# power.net
KiCad netlist of a schematic drawn in Altium Designer
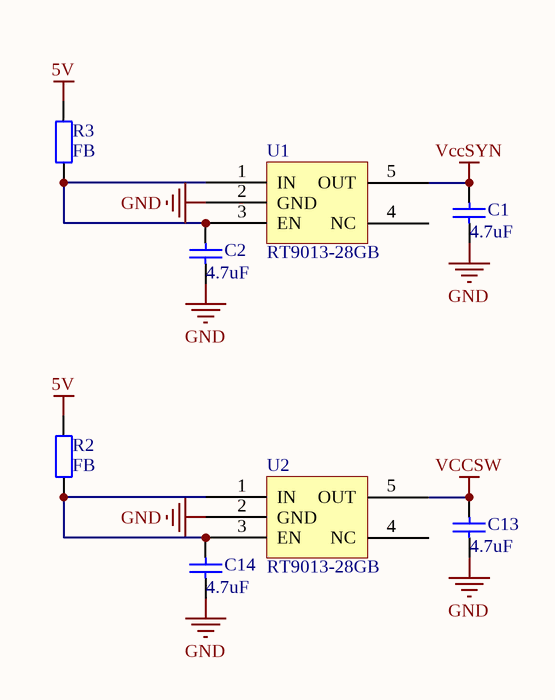
[diagram p0: power.SchDoc]

(export (version "E")
  (design (tool "Eeschema 10.0.6"))
  (components
    (comp (ref "C1")
      (value "4.7uF")
      (footprint "0603")
      (description "Capacitor")
      (fields (field (name "PUBLISHER") "Altium Limited"))
      (libsource (lib "RTC6705") (part "Cap"))
    )
    (comp (ref "C2")
      (value "4.7uF")
      (footprint "0603")
      (description "Capacitor")
      (fields (field (name "PUBLISHER") "Altium Limited"))
      (libsource (lib "RTC6705") (part "Cap"))
    )
    (comp (ref "C13")
      (value "4.7uF")
      (footprint "0603")
      (description "Capacitor")
      (fields (field (name "PUBLISHER") "Altium Limited"))
      (libsource (lib "RTC6705") (part "Cap"))
    )
    (comp (ref "C14")
      (value "4.7uF")
      (footprint "0603")
      (description "Capacitor")
      (fields (field (name "PUBLISHER") "Altium Limited"))
      (libsource (lib "RTC6705") (part "Cap"))
    )
    (comp (ref "R2")
      (value "FB")
      (footprint "0603")
      (description "Resistor")
      (fields (field (name "PUBLISHER") "Altium Limited"))
      (libsource (lib "Miscellaneous Devices") (part "Res2"))
    )
    (comp (ref "R3")
      (value "FB")
      (footprint "0603")
      (description "Resistor")
      (fields (field (name "PUBLISHER") "Altium Limited"))
      (libsource (lib "Miscellaneous Devices") (part "Res2"))
    )
    (comp (ref "U1") (value "RT9013-28GB") (footprint "SOT23-5") (libsource (lib "RTC6705") (part "LP5907")))
    (comp (ref "U2") (value "RT9013-28GB") (footprint "SOT23-5") (libsource (lib "RTC6705") (part "LP5907")))
  )
  (nets
    (net (code "1") (name "5V") (class "Default")
      (node (ref "R2") (pin "2") (pinfunction "2_2") (pintype "passive"))
      (node (ref "R3") (pin "2") (pinfunction "2_2") (pintype "passive"))
    )
    (net (code "2") (name "GND") (class "Default")
      (node (ref "C1") (pin "1") (pinfunction "1_1") (pintype "passive"))
      (node (ref "C13") (pin "1") (pinfunction "1_1") (pintype "passive"))
      (node (ref "C14") (pin "1") (pinfunction "1_1") (pintype "passive"))
      (node (ref "C2") (pin "1") (pinfunction "1_1") (pintype "passive"))
      (node (ref "U1") (pin "2") (pinfunction "GND_2") (pintype "passive"))
      (node (ref "U2") (pin "2") (pinfunction "GND_2") (pintype "passive"))
    )
    (net (code "3") (name "Net-(U1-EN)") (class "Default")
      (node (ref "C2") (pin "2") (pinfunction "2_2") (pintype "passive"))
      (node (ref "R3") (pin "1") (pinfunction "1_1") (pintype "passive"))
      (node (ref "U1") (pin "1") (pinfunction "IN_1") (pintype "passive"))
      (node (ref "U1") (pin "3") (pinfunction "EN_3") (pintype "passive"))
    )
    (net (code "4") (name "Net-(U2-EN)") (class "Default")
      (node (ref "C14") (pin "2") (pinfunction "2_2") (pintype "passive"))
      (node (ref "R2") (pin "1") (pinfunction "1_1") (pintype "passive"))
      (node (ref "U2") (pin "1") (pinfunction "IN_1") (pintype "passive"))
      (node (ref "U2") (pin "3") (pinfunction "EN_3") (pintype "passive"))
    )
    (net (code "5") (name "VCCSW") (class "Default")
      (node (ref "C13") (pin "2") (pinfunction "2_2") (pintype "passive"))
      (node (ref "U2") (pin "5") (pinfunction "OUT_5") (pintype "passive"))
    )
    (net (code "6") (name "VccSYN") (class "Default")
      (node (ref "C1") (pin "2") (pinfunction "2_2") (pintype "passive"))
      (node (ref "U1") (pin "5") (pinfunction "OUT_5") (pintype "passive"))
    )
    (net (code "7") (name "unconnected-(U1-NC-Pad4)") (class "Default")
      (node (ref "U1") (pin "4") (pinfunction "NC_4") (pintype "passive"))
    )
    (net (code "8") (name "unconnected-(U2-NC-Pad4)") (class "Default")
      (node (ref "U2") (pin "4") (pinfunction "NC_4") (pintype "passive"))
    )
  )
)
